# SOIC14.net
KiCad netlist of a schematic drawn in Altium Designer
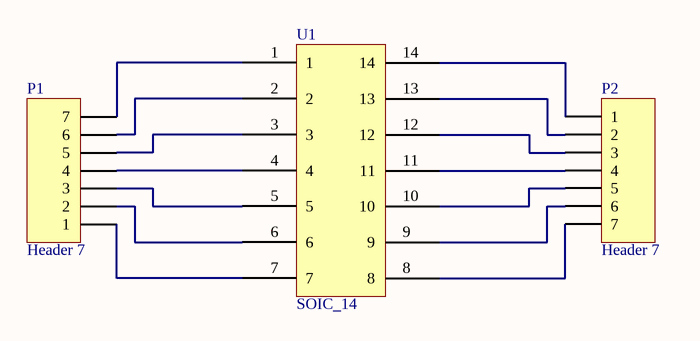
[diagram p0: SOIC14.SchDoc]

(export (version "E")
  (design (tool "Eeschema 10.0.6"))
  (components
    (comp (ref "P1")
      (value "Header 7")
      (footprint "HDR1X7")
      (description "Header, 7-Pin")
      (fields (field (name "PUBLISHER") "Altium Limited"))
      (libsource (lib "") (part "Header 7_1"))
    )
    (comp (ref "P2")
      (value "Header 7")
      (footprint "HDR1X7")
      (description "Header, 7-Pin")
      (fields (field (name "PUBLISHER") "Altium Limited"))
      (libsource (lib "Miscellaneous Connectors") (part "Header 7"))
    )
    (comp (ref "U1")
      (value "SOIC_14")
      (footprint "SOIC14")
      (libsource (lib "PCB_Breakout_Boards") (part "SOIC_14"))
    )
  )
  (nets
    (net (code "1") (name "Net-(P1-Pad1)") (class "Default")
      (node (ref "P1") (pin "1") (pinfunction "1_1") (pintype "passive"))
      (node (ref "U1") (pin "7") (pinfunction "7_7") (pintype "passive"))
    )
    (net (code "2") (name "Net-(P1-Pad2)") (class "Default")
      (node (ref "P1") (pin "2") (pinfunction "2_2") (pintype "passive"))
      (node (ref "U1") (pin "6") (pinfunction "6_6") (pintype "passive"))
    )
    (net (code "3") (name "Net-(P1-Pad3)") (class "Default")
      (node (ref "P1") (pin "3") (pinfunction "3_3") (pintype "passive"))
      (node (ref "U1") (pin "5") (pinfunction "5_5") (pintype "passive"))
    )
    (net (code "4") (name "Net-(P1-Pad4)") (class "Default")
      (node (ref "P1") (pin "4") (pinfunction "4_4") (pintype "passive"))
      (node (ref "U1") (pin "4") (pinfunction "4_4") (pintype "passive"))
    )
    (net (code "5") (name "Net-(P1-Pad5)") (class "Default")
      (node (ref "P1") (pin "5") (pinfunction "5_5") (pintype "passive"))
      (node (ref "U1") (pin "3") (pinfunction "3_3") (pintype "passive"))
    )
    (net (code "6") (name "Net-(P1-Pad6)") (class "Default")
      (node (ref "P1") (pin "6") (pinfunction "6_6") (pintype "passive"))
      (node (ref "U1") (pin "2") (pinfunction "2_2") (pintype "passive"))
    )
    (net (code "7") (name "Net-(P1-Pad7)") (class "Default")
      (node (ref "P1") (pin "7") (pinfunction "7_7") (pintype "passive"))
      (node (ref "U1") (pin "1") (pinfunction "1_1") (pintype "passive"))
    )
    (net (code "8") (name "Net-(P2-Pad1)") (class "Default")
      (node (ref "P2") (pin "1") (pinfunction "1_1") (pintype "passive"))
      (node (ref "U1") (pin "14") (pinfunction "14_14") (pintype "passive"))
    )
    (net (code "9") (name "Net-(P2-Pad2)") (class "Default")
      (node (ref "P2") (pin "2") (pinfunction "2_2") (pintype "passive"))
      (node (ref "U1") (pin "13") (pinfunction "13_13") (pintype "passive"))
    )
    (net (code "10") (name "Net-(P2-Pad3)") (class "Default")
      (node (ref "P2") (pin "3") (pinfunction "3_3") (pintype "passive"))
      (node (ref "U1") (pin "12") (pinfunction "12_12") (pintype "passive"))
    )
    (net (code "11") (name "Net-(P2-Pad4)") (class "Default")
      (node (ref "P2") (pin "4") (pinfunction "4_4") (pintype "passive"))
      (node (ref "U1") (pin "11") (pinfunction "11_11") (pintype "passive"))
    )
    (net (code "12") (name "Net-(P2-Pad5)") (class "Default")
      (node (ref "P2") (pin "5") (pinfunction "5_5") (pintype "passive"))
      (node (ref "U1") (pin "10") (pinfunction "10_10") (pintype "passive"))
    )
    (net (code "13") (name "Net-(P2-Pad6)") (class "Default")
      (node (ref "P2") (pin "6") (pinfunction "6_6") (pintype "passive"))
      (node (ref "U1") (pin "9") (pinfunction "9_9") (pintype "passive"))
    )
    (net (code "14") (name "Net-(P2-Pad7)") (class "Default")
      (node (ref "P2") (pin "7") (pinfunction "7_7") (pintype "passive"))
      (node (ref "U1") (pin "8") (pinfunction "8_8") (pintype "passive"))
    )
  )
)
